# Puzzle_-_IR_distance_interrupter.net
KiCad netlist of a schematic drawn in EAGLE
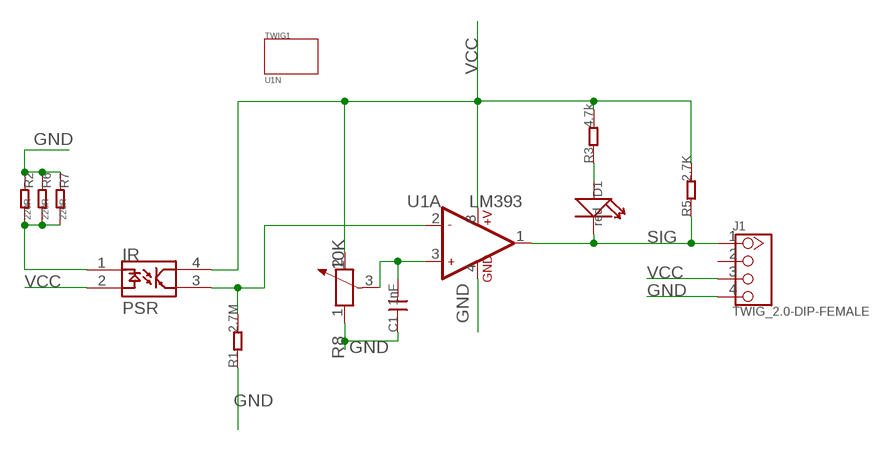
[diagram p0: schematic, sheet 1]

(export (version "E")
  (design (tool "Eeschema 10.0.6"))
  (components
    (comp (ref "C1")
      (value "1nF")
      (footprint "eagle-import:0603")
      (libsource (lib "eagle-import") (part "C-0603"))
    )
    (comp (ref "D1")
      (value "red")
      (footprint "eagle-import:LED0603")
      (libsource (lib "eagle-import") (part "007-LED3540"))
    )
    (comp (ref "J1")
      (value "TWIG_2.0-DIP-FEMALE")
      (footprint "eagle-import:2.0_1X4")
      (libsource (lib "eagle-import") (part "TWIG_2.0-DIP-FEMALE"))
    )
    (comp (ref "PSR")
      (value "PSR")
      (footprint "eagle-import:PSR")
      (libsource (lib "eagle-import") (part "PSR"))
    )
    (comp (ref "R1")
      (value "2.7M")
      (footprint "eagle-import:0603_S")
      (libsource (lib "eagle-import") (part "005-R0603_S"))
    )
    (comp (ref "R2")
      (value "220R")
      (footprint "eagle-import:0805")
      (libsource (lib "eagle-import") (part "R-0805"))
    )
    (comp (ref "R3")
      (value "4.7k")
      (footprint "eagle-import:0603_S")
      (libsource (lib "eagle-import") (part "005-R0603_S"))
    )
    (comp (ref "R5")
      (value "2.7K")
      (footprint "eagle-import:0603_S")
      (libsource (lib "eagle-import") (part "005-R0603_S"))
    )
    (comp (ref "R6")
      (value "220R")
      (footprint "eagle-import:0805")
      (libsource (lib "eagle-import") (part "R-0805"))
    )
    (comp (ref "R7")
      (value "220R")
      (footprint "eagle-import:0805")
      (libsource (lib "eagle-import") (part "R-0805"))
    )
    (comp (ref "R8")
      (value "10K")
      (footprint "eagle-import:3P-SQUA-7X6.8")
      (libsource (lib "eagle-import") (part "R-POTENTIOMETER'3362'"))
    )
    (comp (ref "TWIG1")
      (value "U1N")
      (footprint "eagle-import:U1N")
      (libsource (lib "eagle-import") (part "U1N"))
    )
    (comp (ref "U1")
      (value "LM393")
      (footprint "eagle-import:SO08")
      (libsource (lib "eagle-import") (part "LMV358"))
    )
  )
  (nets
    (net (code "1") (name "/GND") (class "Default")
      (node (ref "C1") (pin "1") (pinfunction "1_1") (pintype "passive"))
      (node (ref "J1") (pin "4") (pinfunction "4_4") (pintype "bidirectional"))
      (node (ref "R1") (pin "1") (pinfunction "1_1") (pintype "passive"))
      (node (ref "R2") (pin "1") (pinfunction "1_1") (pintype "passive"))
      (node (ref "R6") (pin "1") (pinfunction "1_1") (pintype "passive"))
      (node (ref "R7") (pin "1") (pinfunction "1_1") (pintype "passive"))
      (node (ref "R8") (pin "1") (pinfunction "1_1") (pintype "passive"))
      (node (ref "U1") (pin "4") (pinfunction "GND_4") (pintype "power_in"))
    )
    (net (code "2") (name "/SIG") (class "Default")
      (node (ref "D1") (pin "2") (pinfunction "-_2") (pintype "passive"))
      (node (ref "J1") (pin "1") (pinfunction "1_1") (pintype "bidirectional"))
      (node (ref "R5") (pin "1") (pinfunction "1_1") (pintype "passive"))
      (node (ref "U1") (pin "1") (pinfunction "OUT1_1") (pintype "output"))
    )
    (net (code "3") (name "/VCC") (class "Default")
      (node (ref "J1") (pin "3") (pinfunction "3_3") (pintype "bidirectional"))
      (node (ref "PSR") (pin "2") (pinfunction "2_2") (pintype "bidirectional"))
      (node (ref "PSR") (pin "4") (pinfunction "4_4") (pintype "bidirectional"))
      (node (ref "R3") (pin "2") (pinfunction "2_2") (pintype "passive"))
      (node (ref "R5") (pin "2") (pinfunction "2_2") (pintype "passive"))
      (node (ref "R8") (pin "2") (pinfunction "2_2") (pintype "passive"))
      (node (ref "U1") (pin "8") (pinfunction "+V_8") (pintype "power_in"))
    )
    (net (code "4") (name "Net-(D1-+)") (class "Default")
      (node (ref "D1") (pin "1") (pinfunction "+_1") (pintype "passive"))
      (node (ref "R3") (pin "1") (pinfunction "1_1") (pintype "passive"))
    )
    (net (code "5") (name "Net-(PSR-Pad1)") (class "Default")
      (node (ref "PSR") (pin "1") (pinfunction "1_1") (pintype "bidirectional"))
      (node (ref "R2") (pin "2") (pinfunction "2_2") (pintype "passive"))
      (node (ref "R6") (pin "2") (pinfunction "2_2") (pintype "passive"))
      (node (ref "R7") (pin "2") (pinfunction "2_2") (pintype "passive"))
    )
    (net (code "6") (name "Net-(U1A-+IN1)") (class "Default")
      (node (ref "C1") (pin "2") (pinfunction "2_2") (pintype "passive"))
      (node (ref "R8") (pin "3") (pinfunction "3_3") (pintype "passive"))
      (node (ref "U1") (pin "3") (pinfunction "+IN1_3") (pintype "input"))
    )
    (net (code "7") (name "Net-(U1A--IN1)") (class "Default")
      (node (ref "PSR") (pin "3") (pinfunction "3_3") (pintype "bidirectional"))
      (node (ref "R1") (pin "2") (pinfunction "2_2") (pintype "passive"))
      (node (ref "U1") (pin "2") (pinfunction "-IN1_2") (pintype "input"))
    )
    (net (code "8") (name "unconnected-(J1-Pad2)") (class "Default")
      (node (ref "J1") (pin "2") (pinfunction "2_2") (pintype "bidirectional"))
    )
  )
)
